# Xbee_Coordinator.net
KiCad netlist of a schematic drawn in Altium Designer
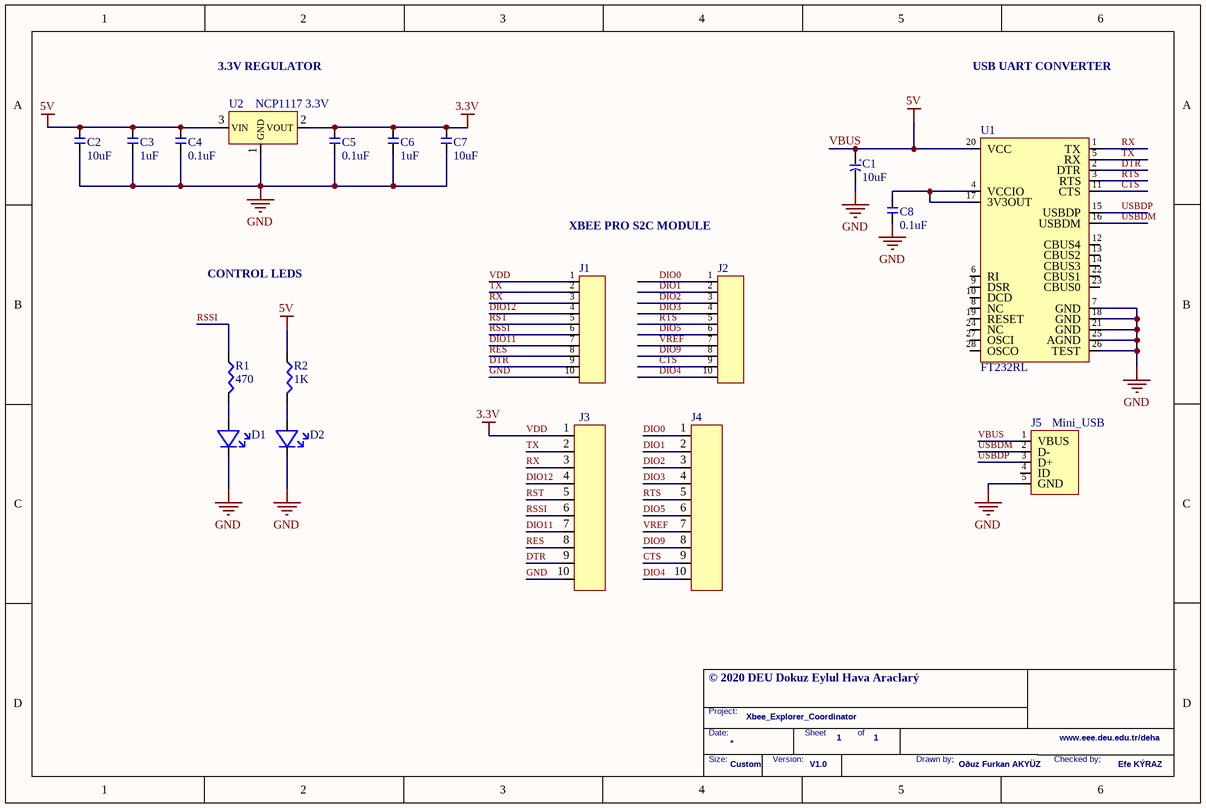
[diagram p0: Xbee_Coordinator.SchDoc]

(export (version "E")
  (design (tool "Eeschema 10.0.6"))
  (components
    (comp (ref "*") (value "TitleBlock") (libsource (lib "Schlib1.~(37).~(9)") (part "TitleBlock")))
    (comp (ref "C1")
      (value "10uF")
      (footprint "5x11 Radial Capacitor")
      (description "5x11 Radial Polarized Capacitor")
      (libsource (lib "Xbee_Co") (part "Cap_Pol_5x11"))
    )
    (comp (ref "C2")
      (value "10uF")
      (footprint "C_1206")
      (description "1206(3216) package capacitor")
      (libsource (lib "Xbee_Co") (part "C_1206(3216)"))
    )
    (comp (ref "C3")
      (value "1uF")
      (footprint "C_1206")
      (description "1206(3216) package capacitor")
      (libsource (lib "Xbee_Co") (part "C_1206(3216)"))
    )
    (comp (ref "C4")
      (value "0.1uF")
      (footprint "C_1206")
      (description "1206(3216) package capacitor")
      (libsource (lib "Xbee_Co") (part "C_1206(3216)"))
    )
    (comp (ref "C5")
      (value "0.1uF")
      (footprint "C_1206")
      (description "1206(3216) package capacitor")
      (libsource (lib "Xbee_Co") (part "C_1206(3216)"))
    )
    (comp (ref "C6")
      (value "1uF")
      (footprint "C_1206")
      (description "1206(3216) package capacitor")
      (libsource (lib "Xbee_Co") (part "C_1206(3216)"))
    )
    (comp (ref "C7")
      (value "10uF")
      (footprint "C_1206")
      (description "1206(3216) package capacitor")
      (libsource (lib "Xbee_Co") (part "C_1206(3216)"))
    )
    (comp (ref "C8")
      (value "0.1uF")
      (footprint "C_1206")
      (description "1206(3216) package capacitor")
      (libsource (lib "Xbee_Co") (part "C_1206(3216)"))
    )
    (comp (ref "D1") (value "LED_0805") (footprint "LED_0805") (libsource (lib "Xbee_Co") (part "LED_0805")))
    (comp (ref "D2") (value "LED_0805") (footprint "LED_0805") (libsource (lib "Xbee_Co") (part "LED_0805")))
    (comp (ref "J1")
      (value "Header_1x10_2mm")
      (footprint "Header 1x10 2mm")
      (libsource (lib "Xbee_Co") (part "Header_1x10_2mm"))
    )
    (comp (ref "J2")
      (value "Header_1x10_2mm")
      (footprint "Header 1x10 2mm")
      (libsource (lib "Xbee_Co") (part "Header_1x10_2mm"))
    )
    (comp (ref "J3")
      (value "Pin_Header_1x10Pos_2.54mm")
      (footprint "PinHeader_1x10Pin_2.54mm")
      (libsource (lib "Xbee_Co") (part "Pin_Header_1x10Pos_2.54mm"))
    )
    (comp (ref "J4")
      (value "Pin_Header_1x10Pos_2.54mm")
      (footprint "PinHeader_1x10Pin_2.54mm")
      (libsource (lib "Xbee_Co") (part "Pin_Header_1x10Pos_2.54mm"))
    )
    (comp (ref "J5") (value "Mini_USB") (footprint "Mini_USB") (libsource (lib "Xbee_Co") (part "Mini_USB")))
    (comp (ref "R1")
      (value "470")
      (footprint "R_1206")
      (description "1206(3216) package resistor")
      (libsource (lib "Xbee_Co") (part "R_1206(3216)"))
    )
    (comp (ref "R2")
      (value "1K")
      (footprint "R_1206")
      (description "1206(3216) package resistor")
      (libsource (lib "Xbee_Co") (part "R_1206(3216)"))
    )
    (comp (ref "U1")
      (value "FT232RL")
      (footprint "SSOP-28Pin")
      (description "FT232RL_USB-Converter")
      (libsource (lib "Xbee_Co") (part "FT232RL"))
    )
    (comp (ref "U2")
      (value "NCP1117 3.3V")
      (footprint "NCP1117 3.3V")
      (description "NCP1117-3.3V Linear Regulator")
      (libsource (lib "Xbee_Co") (part "NCP1117 3.3V"))
    )
  )
  (nets
    (net (code "1") (name "/CTS") (class "Default")
      (node (ref "J2") (pin "9") (pinfunction "9_9") (pintype "passive"))
      (node (ref "J4") (pin "9") (pinfunction "9_9") (pintype "passive"))
      (node (ref "U1") (pin "11") (pinfunction "CTS_11") (pintype "passive"))
    )
    (net (code "2") (name "/DIO0") (class "Default")
      (node (ref "J2") (pin "1") (pinfunction "1_1") (pintype "passive"))
      (node (ref "J4") (pin "1") (pinfunction "11_1") (pintype "passive"))
    )
    (net (code "3") (name "/DIO1") (class "Default")
      (node (ref "J2") (pin "2") (pinfunction "2_2") (pintype "passive"))
      (node (ref "J4") (pin "2") (pinfunction "12_2") (pintype "passive"))
    )
    (net (code "4") (name "/DIO2") (class "Default")
      (node (ref "J2") (pin "3") (pinfunction "3_3") (pintype "passive"))
      (node (ref "J4") (pin "3") (pinfunction "13_3") (pintype "passive"))
    )
    (net (code "5") (name "/DIO3") (class "Default")
      (node (ref "J2") (pin "4") (pinfunction "4_4") (pintype "passive"))
      (node (ref "J4") (pin "4") (pinfunction "14_4") (pintype "passive"))
    )
    (net (code "6") (name "/DIO4") (class "Default")
      (node (ref "J2") (pin "10") (pinfunction "10_10") (pintype "passive"))
      (node (ref "J4") (pin "10") (pinfunction "10_10") (pintype "passive"))
    )
    (net (code "7") (name "/DIO5") (class "Default")
      (node (ref "J2") (pin "6") (pinfunction "6_6") (pintype "passive"))
      (node (ref "J4") (pin "6") (pinfunction "6_6") (pintype "passive"))
    )
    (net (code "8") (name "/DIO9") (class "Default")
      (node (ref "J2") (pin "8") (pinfunction "8_8") (pintype "passive"))
      (node (ref "J4") (pin "8") (pinfunction "8_8") (pintype "passive"))
    )
    (net (code "9") (name "/DIO11") (class "Default")
      (node (ref "J1") (pin "7") (pinfunction "7_7") (pintype "passive"))
      (node (ref "J3") (pin "7") (pinfunction "7_7") (pintype "passive"))
    )
    (net (code "10") (name "/DIO12") (class "Default")
      (node (ref "J1") (pin "4") (pinfunction "4_4") (pintype "passive"))
      (node (ref "J3") (pin "4") (pinfunction "14_4") (pintype "passive"))
    )
    (net (code "11") (name "/DTR") (class "Default")
      (node (ref "J1") (pin "9") (pinfunction "9_9") (pintype "passive"))
      (node (ref "J3") (pin "9") (pinfunction "9_9") (pintype "passive"))
      (node (ref "U1") (pin "2") (pinfunction "DTR_2") (pintype "passive"))
    )
    (net (code "12") (name "/RES") (class "Default")
      (node (ref "J1") (pin "8") (pinfunction "8_8") (pintype "passive"))
      (node (ref "J3") (pin "8") (pinfunction "8_8") (pintype "passive"))
    )
    (net (code "13") (name "/RSSI") (class "Default")
      (node (ref "J1") (pin "6") (pinfunction "6_6") (pintype "passive"))
      (node (ref "J3") (pin "6") (pinfunction "6_6") (pintype "passive"))
      (node (ref "R1") (pin "1") (pinfunction "4_1") (pintype "passive"))
    )
    (net (code "14") (name "/RST") (class "Default")
      (node (ref "J1") (pin "5") (pinfunction "5_5") (pintype "passive"))
      (node (ref "J3") (pin "5") (pinfunction "5_5") (pintype "passive"))
    )
    (net (code "15") (name "/RTS") (class "Default")
      (node (ref "J2") (pin "5") (pinfunction "5_5") (pintype "passive"))
      (node (ref "J4") (pin "5") (pinfunction "5_5") (pintype "passive"))
      (node (ref "U1") (pin "3") (pinfunction "RTS_3") (pintype "passive"))
    )
    (net (code "16") (name "/RX") (class "Default")
      (node (ref "J1") (pin "3") (pinfunction "3_3") (pintype "passive"))
      (node (ref "J3") (pin "3") (pinfunction "13_3") (pintype "passive"))
      (node (ref "U1") (pin "1") (pinfunction "TX_1") (pintype "passive"))
    )
    (net (code "17") (name "/TX") (class "Default")
      (node (ref "J1") (pin "2") (pinfunction "2_2") (pintype "passive"))
      (node (ref "J3") (pin "2") (pinfunction "12_2") (pintype "passive"))
      (node (ref "U1") (pin "5") (pinfunction "RX_5") (pintype "passive"))
    )
    (net (code "18") (name "/USBDM") (class "Default")
      (node (ref "J5") (pin "2") (pinfunction "D-_2") (pintype "passive"))
      (node (ref "U1") (pin "16") (pinfunction "USBDM_16") (pintype "passive"))
    )
    (net (code "19") (name "/USBDP") (class "Default")
      (node (ref "J5") (pin "3") (pinfunction "D+_3") (pintype "passive"))
      (node (ref "U1") (pin "15") (pinfunction "USBDP_15") (pintype "passive"))
    )
    (net (code "20") (name "/VREF") (class "Default")
      (node (ref "J2") (pin "7") (pinfunction "7_7") (pintype "passive"))
      (node (ref "J4") (pin "7") (pinfunction "7_7") (pintype "passive"))
    )
    (net (code "21") (name "3.3V") (class "Default")
      (node (ref "C5") (pin "2") (pinfunction "8_2") (pintype "passive"))
      (node (ref "C6") (pin "2") (pinfunction "8_2") (pintype "passive"))
      (node (ref "C7") (pin "2") (pinfunction "8_2") (pintype "passive"))
      (node (ref "J1") (pin "1") (pinfunction "1_1") (pintype "passive"))
      (node (ref "J3") (pin "1") (pinfunction "11_1") (pintype "passive"))
      (node (ref "U2") (pin "2") (pinfunction "VOUT_2") (pintype "passive"))
    )
    (net (code "22") (name "5V") (class "Default")
      (node (ref "C1") (pin "1") (pinfunction "11_1") (pintype "passive"))
      (node (ref "C2") (pin "2") (pinfunction "8_2") (pintype "passive"))
      (node (ref "C3") (pin "2") (pinfunction "8_2") (pintype "passive"))
      (node (ref "C4") (pin "2") (pinfunction "8_2") (pintype "passive"))
      (node (ref "J5") (pin "1") (pinfunction "VBUS_1") (pintype "passive"))
      (node (ref "R2") (pin "1") (pinfunction "4_1") (pintype "passive"))
      (node (ref "U1") (pin "20") (pinfunction "VCC_20") (pintype "passive"))
      (node (ref "U2") (pin "3") (pinfunction "VIN_3") (pintype "passive"))
    )
    (net (code "23") (name "GND") (class "Default")
      (node (ref "C1") (pin "2") (pinfunction "12_2") (pintype "passive"))
      (node (ref "C2") (pin "1") (pinfunction "7_1") (pintype "passive"))
      (node (ref "C3") (pin "1") (pinfunction "7_1") (pintype "passive"))
      (node (ref "C4") (pin "1") (pinfunction "7_1") (pintype "passive"))
      (node (ref "C5") (pin "1") (pinfunction "7_1") (pintype "passive"))
      (node (ref "C6") (pin "1") (pinfunction "7_1") (pintype "passive"))
      (node (ref "C7") (pin "1") (pinfunction "7_1") (pintype "passive"))
      (node (ref "C8") (pin "1") (pinfunction "7_1") (pintype "passive"))
      (node (ref "D1") (pin "2") (pinfunction "10_2") (pintype "passive"))
      (node (ref "D2") (pin "2") (pinfunction "10_2") (pintype "passive"))
      (node (ref "J1") (pin "10") (pinfunction "10_10") (pintype "passive"))
      (node (ref "J3") (pin "10") (pinfunction "10_10") (pintype "passive"))
      (node (ref "J5") (pin "5") (pinfunction "GND_5") (pintype "passive"))
      (node (ref "U1") (pin "18") (pinfunction "GND_18") (pintype "passive"))
      (node (ref "U1") (pin "21") (pinfunction "GND_21") (pintype "passive"))
      (node (ref "U1") (pin "25") (pinfunction "AGND_25") (pintype "passive"))
      (node (ref "U1") (pin "26") (pinfunction "TEST_26") (pintype "passive"))
      (node (ref "U1") (pin "7") (pinfunction "GND_7") (pintype "passive"))
      (node (ref "U2") (pin "1") (pinfunction "GND_1") (pintype "passive"))
    )
    (net (code "24") (name "Net-(C8-8)") (class "Default")
      (node (ref "C8") (pin "2") (pinfunction "8_2") (pintype "passive"))
      (node (ref "U1") (pin "17") (pinfunction "3V3OUT_17") (pintype "passive"))
      (node (ref "U1") (pin "4") (pinfunction "VCCIO_4") (pintype "passive"))
    )
    (net (code "25") (name "Net-(D1-9)") (class "Default")
      (node (ref "D1") (pin "1") (pinfunction "9_1") (pintype "passive"))
      (node (ref "R1") (pin "2") (pinfunction "5_2") (pintype "passive"))
    )
    (net (code "26") (name "Net-(D2-9)") (class "Default")
      (node (ref "D2") (pin "1") (pinfunction "9_1") (pintype "passive"))
      (node (ref "R2") (pin "2") (pinfunction "5_2") (pintype "passive"))
    )
    (net (code "27") (name "unconnected-(J5-ID-Pad4)") (class "Default")
      (node (ref "J5") (pin "4") (pinfunction "ID_4") (pintype "passive"))
    )
    (net (code "28") (name "unconnected-(U1-CBUS0-Pad23)") (class "Default")
      (node (ref "U1") (pin "23") (pinfunction "CBUS0_23") (pintype "passive"))
    )
    (net (code "29") (name "unconnected-(U1-CBUS1-Pad22)") (class "Default")
      (node (ref "U1") (pin "22") (pinfunction "CBUS1_22") (pintype "passive"))
    )
    (net (code "30") (name "unconnected-(U1-CBUS2-Pad13)") (class "Default")
      (node (ref "U1") (pin "13") (pinfunction "CBUS2_13") (pintype "passive"))
    )
    (net (code "31") (name "unconnected-(U1-CBUS3-Pad14)") (class "Default")
      (node (ref "U1") (pin "14") (pinfunction "CBUS3_14") (pintype "passive"))
    )
    (net (code "32") (name "unconnected-(U1-CBUS4-Pad12)") (class "Default")
      (node (ref "U1") (pin "12") (pinfunction "CBUS4_12") (pintype "passive"))
    )
    (net (code "33") (name "unconnected-(U1-DCD-Pad10)") (class "Default")
      (node (ref "U1") (pin "10") (pinfunction "DCD_10") (pintype "passive"))
    )
    (net (code "34") (name "unconnected-(U1-DSR-Pad9)") (class "Default")
      (node (ref "U1") (pin "9") (pinfunction "DSR_9") (pintype "passive"))
    )
    (net (code "35") (name "unconnected-(U1-NC-Pad8)") (class "Default")
      (node (ref "U1") (pin "8") (pinfunction "NC_8") (pintype "passive"))
    )
    (net (code "36") (name "unconnected-(U1-NC-Pad24)") (class "Default")
      (node (ref "U1") (pin "24") (pinfunction "NC_24") (pintype "passive"))
    )
    (net (code "37") (name "unconnected-(U1-OSCI-Pad27)") (class "Default")
      (node (ref "U1") (pin "27") (pinfunction "OSCI_27") (pintype "passive"))
    )
    (net (code "38") (name "unconnected-(U1-OSCO-Pad28)") (class "Default")
      (node (ref "U1") (pin "28") (pinfunction "OSCO_28") (pintype "passive"))
    )
    (net (code "39") (name "unconnected-(U1-RESET-Pad19)") (class "Default")
      (node (ref "U1") (pin "19") (pinfunction "RESET_19") (pintype "passive"))
    )
    (net (code "40") (name "unconnected-(U1-RI-Pad6)") (class "Default")
      (node (ref "U1") (pin "6") (pinfunction "RI_6") (pintype "passive"))
    )
  )
)
